# input.net
KiCad netlist of a schematic drawn in EAGLE
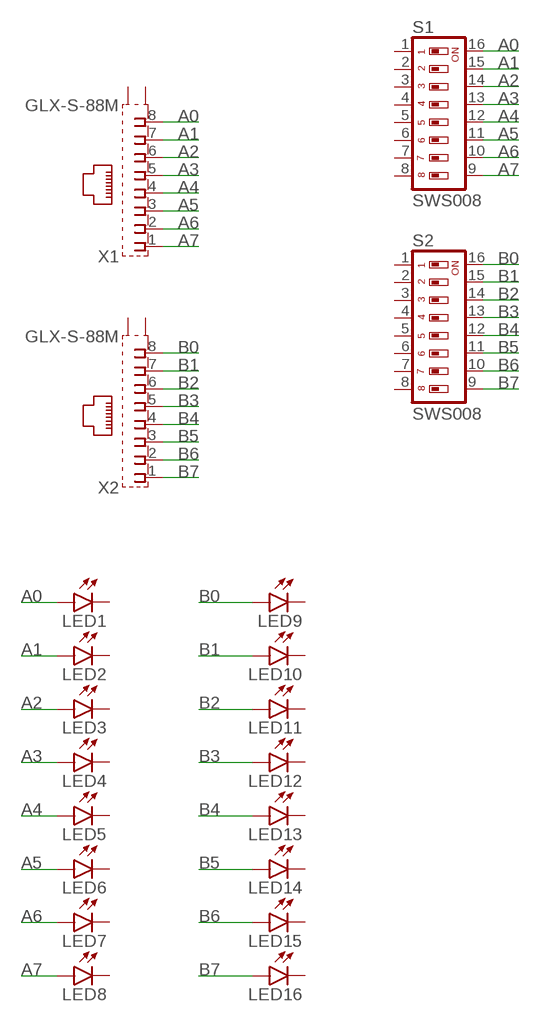
[diagram p0: schematic, sheet 1]

(export (version "E")
  (design (tool "Eeschema 10.0.6"))
  (components
    (comp (ref "LED1")
      (value "LEDSML1206")
      (footprint "eagle-import:SML1206")
      (libsource (lib "eagle-import") (part "LEDSML1206"))
    )
    (comp (ref "LED2")
      (value "LEDSML1206")
      (footprint "eagle-import:SML1206")
      (libsource (lib "eagle-import") (part "LEDSML1206"))
    )
    (comp (ref "LED3")
      (value "LEDSML1206")
      (footprint "eagle-import:SML1206")
      (libsource (lib "eagle-import") (part "LEDSML1206"))
    )
    (comp (ref "LED4")
      (value "LEDSML1206")
      (footprint "eagle-import:SML1206")
      (libsource (lib "eagle-import") (part "LEDSML1206"))
    )
    (comp (ref "LED5")
      (value "LEDSML1206")
      (footprint "eagle-import:SML1206")
      (libsource (lib "eagle-import") (part "LEDSML1206"))
    )
    (comp (ref "LED6")
      (value "LEDSML1206")
      (footprint "eagle-import:SML1206")
      (libsource (lib "eagle-import") (part "LEDSML1206"))
    )
    (comp (ref "LED7")
      (value "LEDSML1206")
      (footprint "eagle-import:SML1206")
      (libsource (lib "eagle-import") (part "LEDSML1206"))
    )
    (comp (ref "LED8")
      (value "LEDSML1206")
      (footprint "eagle-import:SML1206")
      (libsource (lib "eagle-import") (part "LEDSML1206"))
    )
    (comp (ref "LED9")
      (value "LEDSML1206")
      (footprint "eagle-import:SML1206")
      (libsource (lib "eagle-import") (part "LEDSML1206"))
    )
    (comp (ref "LED10")
      (value "LEDSML1206")
      (footprint "eagle-import:SML1206")
      (libsource (lib "eagle-import") (part "LEDSML1206"))
    )
    (comp (ref "LED11")
      (value "LEDSML1206")
      (footprint "eagle-import:SML1206")
      (libsource (lib "eagle-import") (part "LEDSML1206"))
    )
    (comp (ref "LED12")
      (value "LEDSML1206")
      (footprint "eagle-import:SML1206")
      (libsource (lib "eagle-import") (part "LEDSML1206"))
    )
    (comp (ref "LED13")
      (value "LEDSML1206")
      (footprint "eagle-import:SML1206")
      (libsource (lib "eagle-import") (part "LEDSML1206"))
    )
    (comp (ref "LED14")
      (value "LEDSML1206")
      (footprint "eagle-import:SML1206")
      (libsource (lib "eagle-import") (part "LEDSML1206"))
    )
    (comp (ref "LED15")
      (value "LEDSML1206")
      (footprint "eagle-import:SML1206")
      (libsource (lib "eagle-import") (part "LEDSML1206"))
    )
    (comp (ref "LED16")
      (value "LEDSML1206")
      (footprint "eagle-import:SML1206")
      (libsource (lib "eagle-import") (part "LEDSML1206"))
    )
    (comp (ref "S1")
      (value "SWS008")
      (footprint "eagle-import:SMS-008")
      (libsource (lib "eagle-import") (part "SWS008"))
    )
    (comp (ref "S2")
      (value "SWS008")
      (footprint "eagle-import:SMS-008")
      (libsource (lib "eagle-import") (part "SWS008"))
    )
    (comp (ref "X1")
      (value "GLX-S-88M")
      (footprint "eagle-import:GLX-S-88M")
      (libsource (lib "eagle-import") (part "GLX-S-88M"))
    )
    (comp (ref "X2")
      (value "GLX-S-88M")
      (footprint "eagle-import:GLX-S-88M")
      (libsource (lib "eagle-import") (part "GLX-S-88M"))
    )
  )
  (nets
    (net (code "1") (name "/A0") (class "Default")
      (node (ref "LED1") (pin "A") (pinfunction "A_A") (pintype "passive"))
      (node (ref "S1") (pin "16") (pinfunction "16_16") (pintype "passive"))
      (node (ref "X1") (pin "8") (pinfunction "8_8") (pintype "passive"))
    )
    (net (code "2") (name "/A1") (class "Default")
      (node (ref "LED2") (pin "A") (pinfunction "A_A") (pintype "passive"))
      (node (ref "S1") (pin "15") (pinfunction "15_15") (pintype "passive"))
      (node (ref "X1") (pin "7") (pinfunction "7_7") (pintype "passive"))
    )
    (net (code "3") (name "/A2") (class "Default")
      (node (ref "LED3") (pin "A") (pinfunction "A_A") (pintype "passive"))
      (node (ref "S1") (pin "14") (pinfunction "14_14") (pintype "passive"))
      (node (ref "X1") (pin "6") (pinfunction "6_6") (pintype "passive"))
    )
    (net (code "4") (name "/A3") (class "Default")
      (node (ref "LED4") (pin "A") (pinfunction "A_A") (pintype "passive"))
      (node (ref "S1") (pin "13") (pinfunction "13_13") (pintype "passive"))
      (node (ref "X1") (pin "5") (pinfunction "5_5") (pintype "passive"))
    )
    (net (code "5") (name "/A4") (class "Default")
      (node (ref "LED5") (pin "A") (pinfunction "A_A") (pintype "passive"))
      (node (ref "S1") (pin "12") (pinfunction "12_12") (pintype "passive"))
      (node (ref "X1") (pin "4") (pinfunction "4_4") (pintype "passive"))
    )
    (net (code "6") (name "/A5") (class "Default")
      (node (ref "LED6") (pin "A") (pinfunction "A_A") (pintype "passive"))
      (node (ref "S1") (pin "11") (pinfunction "11_11") (pintype "passive"))
      (node (ref "X1") (pin "3") (pinfunction "3_3") (pintype "passive"))
    )
    (net (code "7") (name "/A6") (class "Default")
      (node (ref "LED7") (pin "A") (pinfunction "A_A") (pintype "passive"))
      (node (ref "S1") (pin "10") (pinfunction "10_10") (pintype "passive"))
      (node (ref "X1") (pin "2") (pinfunction "2_2") (pintype "passive"))
    )
    (net (code "8") (name "/A7") (class "Default")
      (node (ref "LED8") (pin "A") (pinfunction "A_A") (pintype "passive"))
      (node (ref "S1") (pin "9") (pinfunction "9_9") (pintype "passive"))
      (node (ref "X1") (pin "1") (pinfunction "1_1") (pintype "passive"))
    )
    (net (code "9") (name "/B0") (class "Default")
      (node (ref "LED9") (pin "A") (pinfunction "A_A") (pintype "passive"))
      (node (ref "S2") (pin "16") (pinfunction "16_16") (pintype "passive"))
      (node (ref "X2") (pin "8") (pinfunction "8_8") (pintype "passive"))
    )
    (net (code "10") (name "/B1") (class "Default")
      (node (ref "LED10") (pin "A") (pinfunction "A_A") (pintype "passive"))
      (node (ref "S2") (pin "15") (pinfunction "15_15") (pintype "passive"))
      (node (ref "X2") (pin "7") (pinfunction "7_7") (pintype "passive"))
    )
    (net (code "11") (name "/B2") (class "Default")
      (node (ref "LED11") (pin "A") (pinfunction "A_A") (pintype "passive"))
      (node (ref "S2") (pin "14") (pinfunction "14_14") (pintype "passive"))
      (node (ref "X2") (pin "6") (pinfunction "6_6") (pintype "passive"))
    )
    (net (code "12") (name "/B3") (class "Default")
      (node (ref "LED12") (pin "A") (pinfunction "A_A") (pintype "passive"))
      (node (ref "S2") (pin "13") (pinfunction "13_13") (pintype "passive"))
      (node (ref "X2") (pin "5") (pinfunction "5_5") (pintype "passive"))
    )
    (net (code "13") (name "/B4") (class "Default")
      (node (ref "LED13") (pin "A") (pinfunction "A_A") (pintype "passive"))
      (node (ref "S2") (pin "12") (pinfunction "12_12") (pintype "passive"))
      (node (ref "X2") (pin "4") (pinfunction "4_4") (pintype "passive"))
    )
    (net (code "14") (name "/B5") (class "Default")
      (node (ref "LED14") (pin "A") (pinfunction "A_A") (pintype "passive"))
      (node (ref "S2") (pin "11") (pinfunction "11_11") (pintype "passive"))
      (node (ref "X2") (pin "3") (pinfunction "3_3") (pintype "passive"))
    )
    (net (code "15") (name "/B6") (class "Default")
      (node (ref "LED15") (pin "A") (pinfunction "A_A") (pintype "passive"))
      (node (ref "S2") (pin "10") (pinfunction "10_10") (pintype "passive"))
      (node (ref "X2") (pin "2") (pinfunction "2_2") (pintype "passive"))
    )
    (net (code "16") (name "/B7") (class "Default")
      (node (ref "LED16") (pin "A") (pinfunction "A_A") (pintype "passive"))
      (node (ref "S2") (pin "9") (pinfunction "9_9") (pintype "passive"))
      (node (ref "X2") (pin "1") (pinfunction "1_1") (pintype "passive"))
    )
    (net (code "17") (name "unconnected-(LED1-PadC)") (class "Default")
      (node (ref "LED1") (pin "C") (pinfunction "C_C") (pintype "passive"))
    )
    (net (code "18") (name "unconnected-(LED2-PadC)") (class "Default")
      (node (ref "LED2") (pin "C") (pinfunction "C_C") (pintype "passive"))
    )
    (net (code "19") (name "unconnected-(LED3-PadC)") (class "Default")
      (node (ref "LED3") (pin "C") (pinfunction "C_C") (pintype "passive"))
    )
    (net (code "20") (name "unconnected-(LED4-PadC)") (class "Default")
      (node (ref "LED4") (pin "C") (pinfunction "C_C") (pintype "passive"))
    )
    (net (code "21") (name "unconnected-(LED5-PadC)") (class "Default")
      (node (ref "LED5") (pin "C") (pinfunction "C_C") (pintype "passive"))
    )
    (net (code "22") (name "unconnected-(LED6-PadC)") (class "Default")
      (node (ref "LED6") (pin "C") (pinfunction "C_C") (pintype "passive"))
    )
    (net (code "23") (name "unconnected-(LED7-PadC)") (class "Default")
      (node (ref "LED7") (pin "C") (pinfunction "C_C") (pintype "passive"))
    )
    (net (code "24") (name "unconnected-(LED8-PadC)") (class "Default")
      (node (ref "LED8") (pin "C") (pinfunction "C_C") (pintype "passive"))
    )
    (net (code "25") (name "unconnected-(LED9-PadC)") (class "Default")
      (node (ref "LED9") (pin "C") (pinfunction "C_C") (pintype "passive"))
    )
    (net (code "26") (name "unconnected-(LED10-PadC)") (class "Default")
      (node (ref "LED10") (pin "C") (pinfunction "C_C") (pintype "passive"))
    )
    (net (code "27") (name "unconnected-(LED11-PadC)") (class "Default")
      (node (ref "LED11") (pin "C") (pinfunction "C_C") (pintype "passive"))
    )
    (net (code "28") (name "unconnected-(LED12-PadC)") (class "Default")
      (node (ref "LED12") (pin "C") (pinfunction "C_C") (pintype "passive"))
    )
    (net (code "29") (name "unconnected-(LED13-PadC)") (class "Default")
      (node (ref "LED13") (pin "C") (pinfunction "C_C") (pintype "passive"))
    )
    (net (code "30") (name "unconnected-(LED14-PadC)") (class "Default")
      (node (ref "LED14") (pin "C") (pinfunction "C_C") (pintype "passive"))
    )
    (net (code "31") (name "unconnected-(LED15-PadC)") (class "Default")
      (node (ref "LED15") (pin "C") (pinfunction "C_C") (pintype "passive"))
    )
    (net (code "32") (name "unconnected-(LED16-PadC)") (class "Default")
      (node (ref "LED16") (pin "C") (pinfunction "C_C") (pintype "passive"))
    )
    (net (code "33") (name "unconnected-(S1-Pad1)") (class "Default")
      (node (ref "S1") (pin "1") (pinfunction "1_1") (pintype "passive"))
    )
    (net (code "34") (name "unconnected-(S1-Pad2)") (class "Default")
      (node (ref "S1") (pin "2") (pinfunction "2_2") (pintype "passive"))
    )
    (net (code "35") (name "unconnected-(S1-Pad3)") (class "Default")
      (node (ref "S1") (pin "3") (pinfunction "3_3") (pintype "passive"))
    )
    (net (code "36") (name "unconnected-(S1-Pad4)") (class "Default")
      (node (ref "S1") (pin "4") (pinfunction "4_4") (pintype "passive"))
    )
    (net (code "37") (name "unconnected-(S1-Pad5)") (class "Default")
      (node (ref "S1") (pin "5") (pinfunction "5_5") (pintype "passive"))
    )
    (net (code "38") (name "unconnected-(S1-Pad6)") (class "Default")
      (node (ref "S1") (pin "6") (pinfunction "6_6") (pintype "passive"))
    )
    (net (code "39") (name "unconnected-(S1-Pad7)") (class "Default")
      (node (ref "S1") (pin "7") (pinfunction "7_7") (pintype "passive"))
    )
    (net (code "40") (name "unconnected-(S1-Pad8)") (class "Default")
      (node (ref "S1") (pin "8") (pinfunction "8_8") (pintype "passive"))
    )
    (net (code "41") (name "unconnected-(S2-Pad1)") (class "Default")
      (node (ref "S2") (pin "1") (pinfunction "1_1") (pintype "passive"))
    )
    (net (code "42") (name "unconnected-(S2-Pad2)") (class "Default")
      (node (ref "S2") (pin "2") (pinfunction "2_2") (pintype "passive"))
    )
    (net (code "43") (name "unconnected-(S2-Pad3)") (class "Default")
      (node (ref "S2") (pin "3") (pinfunction "3_3") (pintype "passive"))
    )
    (net (code "44") (name "unconnected-(S2-Pad4)") (class "Default")
      (node (ref "S2") (pin "4") (pinfunction "4_4") (pintype "passive"))
    )
    (net (code "45") (name "unconnected-(S2-Pad5)") (class "Default")
      (node (ref "S2") (pin "5") (pinfunction "5_5") (pintype "passive"))
    )
    (net (code "46") (name "unconnected-(S2-Pad6)") (class "Default")
      (node (ref "S2") (pin "6") (pinfunction "6_6") (pintype "passive"))
    )
    (net (code "47") (name "unconnected-(S2-Pad7)") (class "Default")
      (node (ref "S2") (pin "7") (pinfunction "7_7") (pintype "passive"))
    )
    (net (code "48") (name "unconnected-(S2-Pad8)") (class "Default")
      (node (ref "S2") (pin "8") (pinfunction "8_8") (pintype "passive"))
    )
    (net (code "49") (name "unconnected-(X1-PadS1)") (class "Default")
      (node (ref "X1") (pin "S1") (pinfunction "S1_S1") (pintype "passive"))
    )
    (net (code "50") (name "unconnected-(X1-PadS2)") (class "Default")
      (node (ref "X1") (pin "S2") (pinfunction "S2_S2") (pintype "passive"))
    )
    (net (code "51") (name "unconnected-(X2-PadS1)") (class "Default")
      (node (ref "X2") (pin "S1") (pinfunction "S1_S1") (pintype "passive"))
    )
    (net (code "52") (name "unconnected-(X2-PadS2)") (class "Default")
      (node (ref "X2") (pin "S2") (pinfunction "S2_S2") (pintype "passive"))
    )
  )
)
